# SCH_Pcb_Tof_Robocup_Joaquin_2023-06-20.net
KiCad netlist of a schematic drawn in EasyEDA
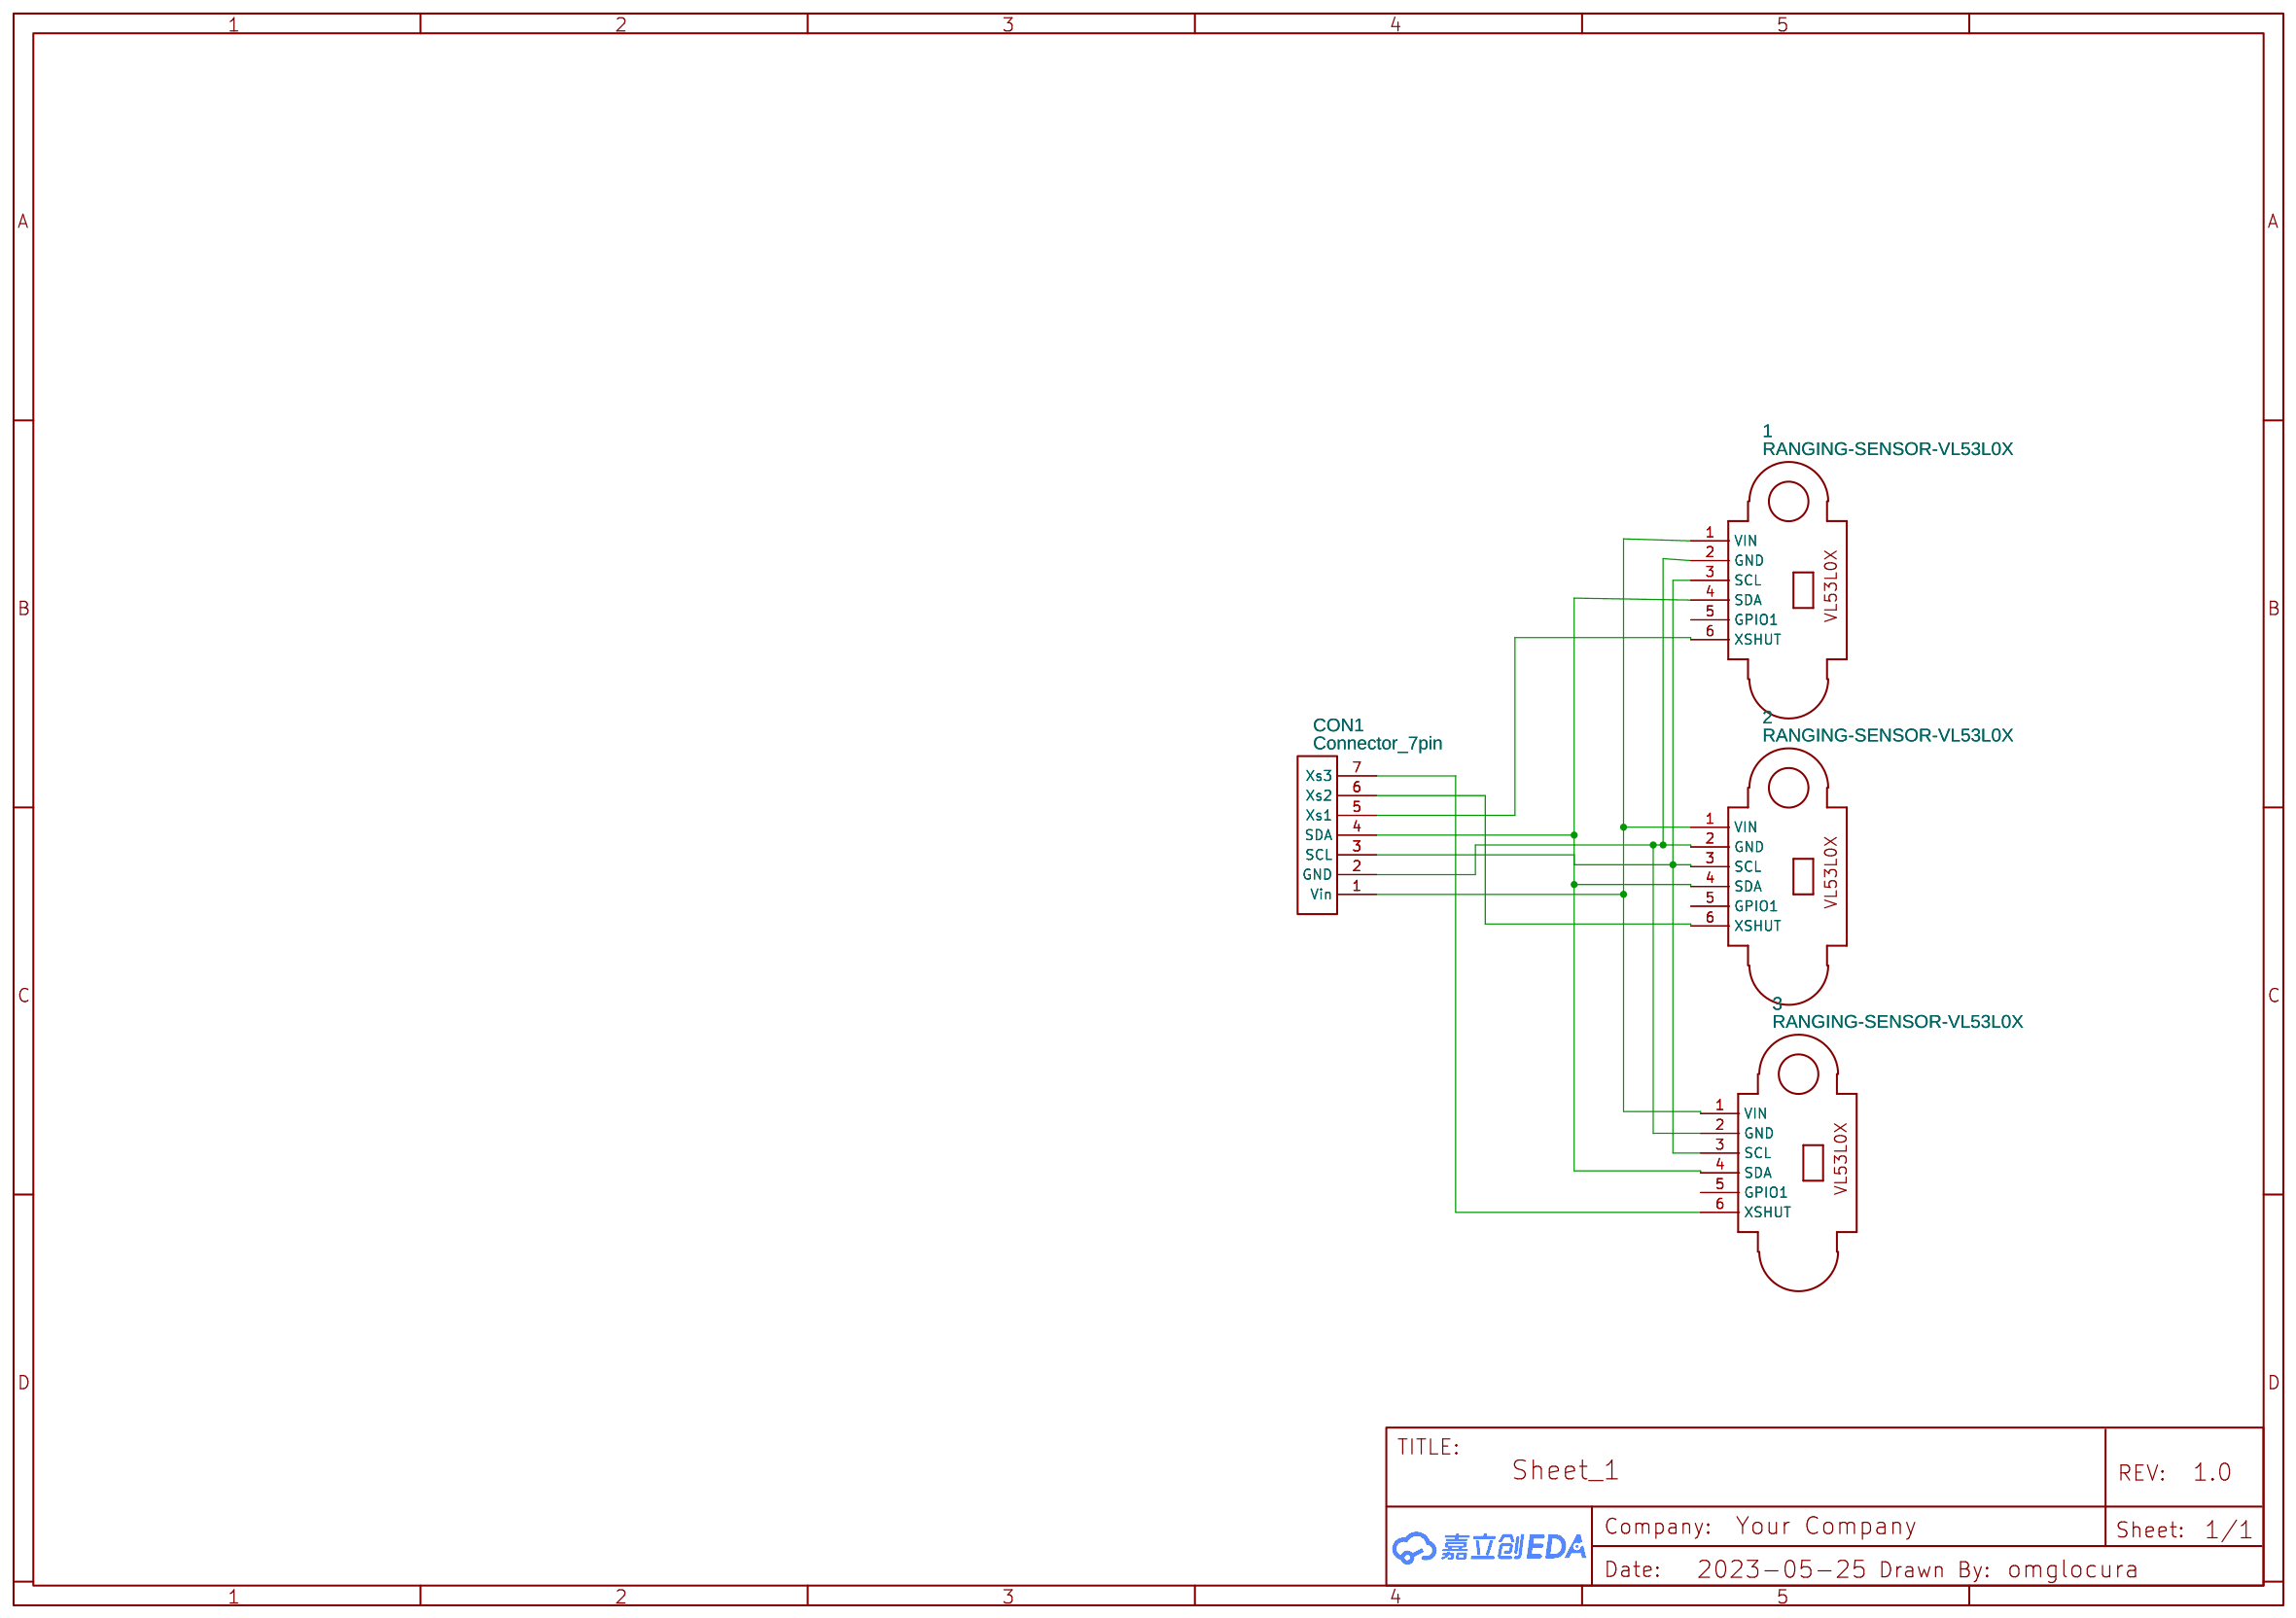
[diagram p0: schematic sheet]

(export (version "E")
  (design (tool "Eeschema 10.0.6"))
  (components
    (comp (ref "1") (value "RANGING-SENSOR-VL53L0X") (libsource (lib "") (part "RANGING-SENSOR-VL53L0X")))
    (comp (ref "2") (value "RANGING-SENSOR-VL53L0X") (libsource (lib "") (part "RANGING-SENSOR-VL53L0X")))
    (comp (ref "3") (value "RANGING-SENSOR-VL53L0X") (libsource (lib "") (part "RANGING-SENSOR-VL53L0X")))
    (comp (ref "CON1") (value "Connector_7pin") (libsource (lib "") (part "Connector_7pin")))
  )
  (nets
    (net (code "1") (name "Net-(1-GND)") (class "Default")
      (node (ref "1") (pin "2") (pinfunction "GND_2") (pintype "bidirectional"))
      (node (ref "2") (pin "2") (pinfunction "GND_2") (pintype "bidirectional"))
      (node (ref "3") (pin "2") (pinfunction "GND_2") (pintype "bidirectional"))
      (node (ref "CON1") (pin "2") (pinfunction "GND_2") (pintype "unspecified"))
    )
    (net (code "2") (name "Net-(1-SCL)") (class "Default")
      (node (ref "1") (pin "3") (pinfunction "SCL_3") (pintype "bidirectional"))
      (node (ref "2") (pin "3") (pinfunction "SCL_3") (pintype "bidirectional"))
      (node (ref "3") (pin "3") (pinfunction "SCL_3") (pintype "bidirectional"))
      (node (ref "CON1") (pin "3") (pinfunction "SCL_3") (pintype "unspecified"))
    )
    (net (code "3") (name "Net-(1-SDA)") (class "Default")
      (node (ref "1") (pin "4") (pinfunction "SDA_4") (pintype "bidirectional"))
      (node (ref "2") (pin "4") (pinfunction "SDA_4") (pintype "bidirectional"))
      (node (ref "3") (pin "4") (pinfunction "SDA_4") (pintype "bidirectional"))
      (node (ref "CON1") (pin "4") (pinfunction "SDA_4") (pintype "unspecified"))
    )
    (net (code "4") (name "Net-(1-VIN)") (class "Default")
      (node (ref "1") (pin "1") (pinfunction "VIN_1") (pintype "bidirectional"))
      (node (ref "2") (pin "1") (pinfunction "VIN_1") (pintype "bidirectional"))
      (node (ref "3") (pin "1") (pinfunction "VIN_1") (pintype "bidirectional"))
      (node (ref "CON1") (pin "1") (pinfunction "Vin_1") (pintype "unspecified"))
    )
    (net (code "5") (name "Net-(1-XSHUT)") (class "Default")
      (node (ref "1") (pin "6") (pinfunction "XSHUT_6") (pintype "bidirectional"))
      (node (ref "CON1") (pin "5") (pinfunction "Xs1_5") (pintype "unspecified"))
    )
    (net (code "6") (name "Net-(2-XSHUT)") (class "Default")
      (node (ref "2") (pin "6") (pinfunction "XSHUT_6") (pintype "bidirectional"))
      (node (ref "CON1") (pin "6") (pinfunction "Xs2_6") (pintype "unspecified"))
    )
    (net (code "7") (name "Net-(3-XSHUT)") (class "Default")
      (node (ref "3") (pin "6") (pinfunction "XSHUT_6") (pintype "bidirectional"))
      (node (ref "CON1") (pin "7") (pinfunction "Xs3_7") (pintype "unspecified"))
    )
    (net (code "8") (name "unconnected-(1-GPIO1-Pad5)") (class "Default")
      (node (ref "1") (pin "5") (pinfunction "GPIO1_5") (pintype "bidirectional"))
    )
    (net (code "9") (name "unconnected-(2-GPIO1-Pad5)") (class "Default")
      (node (ref "2") (pin "5") (pinfunction "GPIO1_5") (pintype "bidirectional"))
    )
    (net (code "10") (name "unconnected-(3-GPIO1-Pad5)") (class "Default")
      (node (ref "3") (pin "5") (pinfunction "GPIO1_5") (pintype "bidirectional"))
    )
  )
)
